# Rev3b_Schematic.net
KiCad netlist of a schematic drawn in Altium Designer
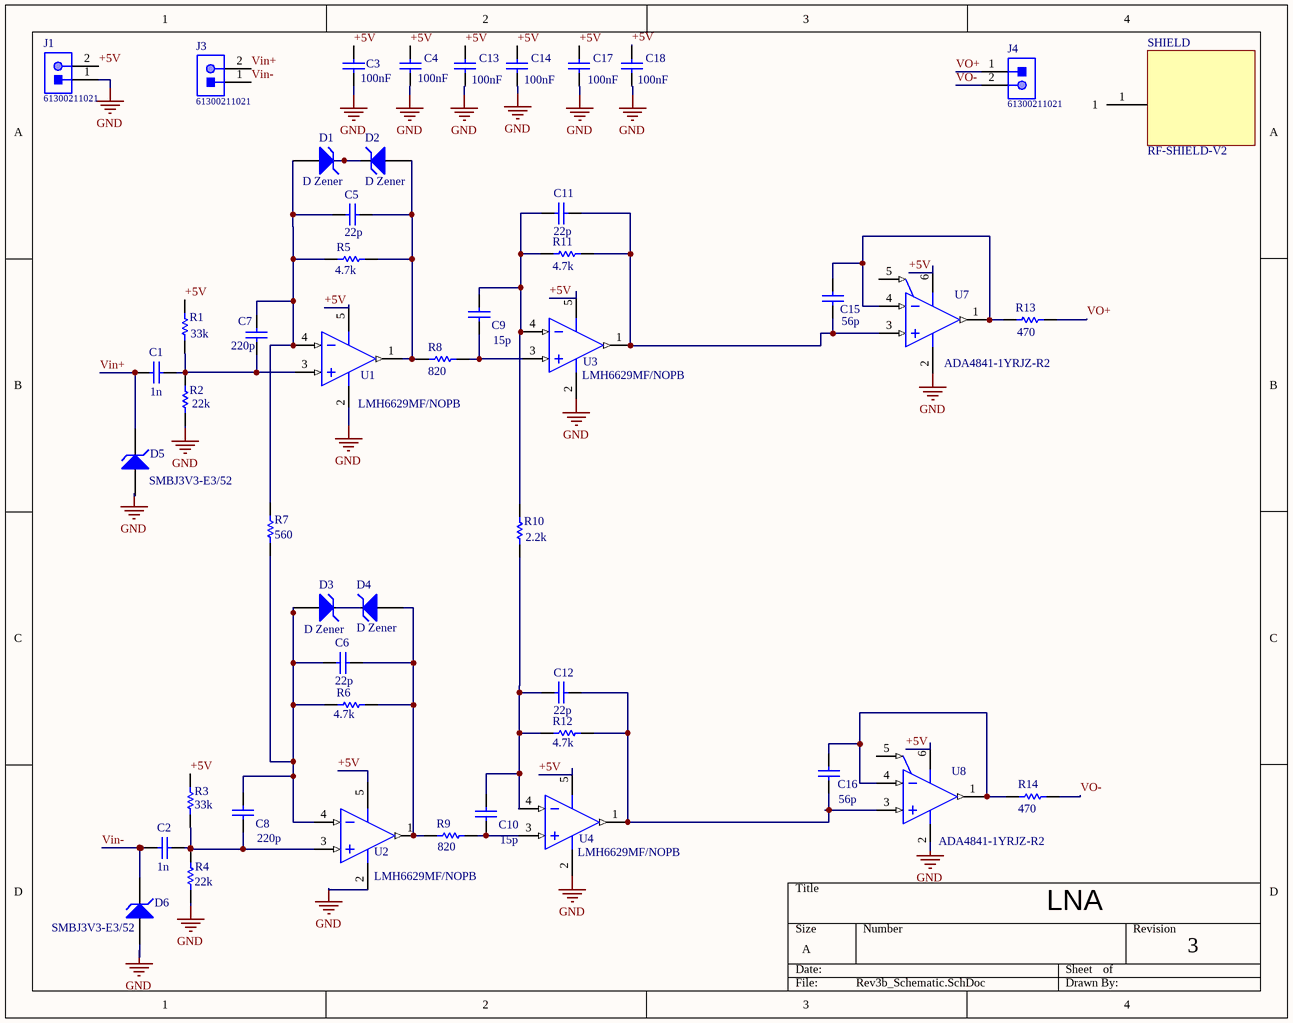
[diagram p0: Rev3b_Schematic.SchDoc]

(export (version "E")
  (design (tool "Eeschema 10.0.6"))
  (components
    (comp (ref "C1")
      (value "1n")
      (footprint "*CAPC1608X90")
      (description "Capacitor")
      (fields (field (name "PUBLISHER") "Altium Limited"))
      (libsource (lib "Miscellaneous Devices") (part "Cap"))
    )
    (comp (ref "C2")
      (value "1n")
      (footprint "*CAPC1608X90")
      (description "Capacitor")
      (fields (field (name "PUBLISHER") "Altium Limited"))
      (libsource (lib "Miscellaneous Devices") (part "Cap"))
    )
    (comp (ref "C3")
      (value "100nF")
      (footprint "*CAPC1608X90")
      (description "Capacitor")
      (fields (field (name "PUBLISHER") "Altium Limited"))
      (libsource (lib "Miscellaneous Devices") (part "Cap"))
    )
    (comp (ref "C4")
      (value "100nF")
      (footprint "*CAPC1608X90")
      (description "Capacitor")
      (fields (field (name "PUBLISHER") "Altium Limited"))
      (libsource (lib "Miscellaneous Devices") (part "Cap"))
    )
    (comp (ref "C5")
      (value "22p")
      (footprint "CAPC1608X90X35LL10T15")
      (fields (field (name "PART NUMBER") "GRM1885C1H100JA01D") (field (name "MANUFACTURER") "Murata"))
      (libsource (lib "Altium Content Vault") (part "CAP"))
    )
    (comp (ref "C6")
      (value "22p")
      (footprint "CAPC1608X90X35LL10T15")
      (fields (field (name "PART NUMBER") "GRM1885C1H100JA01D") (field (name "MANUFACTURER") "Murata"))
      (libsource (lib "Altium Content Vault") (part "CAP"))
    )
    (comp (ref "C7")
      (value "220p")
      (footprint "CAPC1608X87X35NL15T15")
      (fields (field (name "PART NUMBER") "C0603C331J5GACTU") (field (name "MANUFACTURER") "Kemet"))
      (libsource (lib "Altium Content Vault") (part "CAP"))
    )
    (comp (ref "C8")
      (value "220p")
      (footprint "CAPC1608X87X35NL15T15")
      (fields (field (name "PART NUMBER") "C0603C331J5GACTU") (field (name "MANUFACTURER") "Kemet"))
      (libsource (lib "Altium Content Vault") (part "CAP"))
    )
    (comp (ref "C9")
      (value "15p")
      (footprint "CAPC1608X87X35NL15T15")
      (fields (field (name "PART NUMBER") "C0603C331J5GACTU") (field (name "MANUFACTURER") "Kemet"))
      (libsource (lib "Altium Content Vault") (part "CAP"))
    )
    (comp (ref "C10")
      (value "15p")
      (footprint "CAPC1608X87X35NL15T15")
      (fields (field (name "PART NUMBER") "C0603C331J5GACTU") (field (name "MANUFACTURER") "Kemet"))
      (libsource (lib "Altium Content Vault") (part "CAP"))
    )
    (comp (ref "C11")
      (value "22p")
      (footprint "CAPC1608X90X35LL10T15")
      (fields (field (name "PART NUMBER") "GRM1885C1H100JA01D") (field (name "MANUFACTURER") "Murata"))
      (libsource (lib "Altium Content Vault") (part "CAP"))
    )
    (comp (ref "C12")
      (value "22p")
      (footprint "CAPC1608X90X35LL10T15")
      (fields (field (name "PART NUMBER") "GRM1885C1H100JA01D") (field (name "MANUFACTURER") "Murata"))
      (libsource (lib "Altium Content Vault") (part "CAP"))
    )
    (comp (ref "C13")
      (value "100nF")
      (footprint "*CAPC1608X90")
      (description "Capacitor")
      (fields (field (name "PUBLISHER") "Altium Limited"))
      (libsource (lib "Miscellaneous Devices") (part "Cap"))
    )
    (comp (ref "C14")
      (value "100nF")
      (footprint "*CAPC1608X90")
      (description "Capacitor")
      (fields (field (name "PUBLISHER") "Altium Limited"))
      (libsource (lib "Miscellaneous Devices") (part "Cap"))
    )
    (comp (ref "C15")
      (value "56p")
      (footprint "CAPC1608X87X35NL15T15")
      (fields (field (name "PART NUMBER") "C0603C331J5GACTU") (field (name "MANUFACTURER") "Kemet"))
      (libsource (lib "Altium Content Vault") (part "CAP"))
    )
    (comp (ref "C16")
      (value "56p")
      (footprint "CAPC1608X87X35NL15T15")
      (fields (field (name "PART NUMBER") "C0603C331J5GACTU") (field (name "MANUFACTURER") "Kemet"))
      (libsource (lib "Altium Content Vault") (part "CAP"))
    )
    (comp (ref "C17")
      (value "100nF")
      (footprint "*CAPC1608X90")
      (description "Capacitor")
      (fields (field (name "PUBLISHER") "Altium Limited"))
      (libsource (lib "Miscellaneous Devices") (part "Cap"))
    )
    (comp (ref "C18")
      (value "100nF")
      (footprint "*CAPC1608X90")
      (description "Capacitor")
      (fields (field (name "PUBLISHER") "Altium Limited"))
      (libsource (lib "Miscellaneous Devices") (part "Cap"))
    )
    (comp (ref "D1")
      (value "D Zener")
      (footprint "J1-0603")
      (description "Zener Diode")
      (fields (field (name "PUBLISHER") "Altium Limited"))
      (libsource (lib "Miscellaneous Devices") (part "D Zener"))
    )
    (comp (ref "D2")
      (value "D Zener")
      (footprint "J1-0603")
      (description "Zener Diode")
      (fields (field (name "PUBLISHER") "Altium Limited"))
      (libsource (lib "Miscellaneous Devices") (part "D Zener"))
    )
    (comp (ref "D3")
      (value "D Zener")
      (footprint "J1-0603")
      (description "Zener Diode")
      (fields (field (name "PUBLISHER") "Altium Limited"))
      (libsource (lib "Miscellaneous Devices") (part "D Zener"))
    )
    (comp (ref "D4")
      (value "D Zener")
      (footprint "J1-0603")
      (description "Zener Diode")
      (fields (field (name "PUBLISHER") "Altium Limited"))
      (libsource (lib "Miscellaneous Devices") (part "D Zener"))
    )
    (comp (ref "D5")
      (value "SMBJ3V3-E3/52")
      (footprint "VISH-DO-214AA-2_V")
      (fields (field (name "MANUFACTURER") "Vishay"))
      (libsource (lib "Altium Content Vault") (part "DZEN-AK-2"))
    )
    (comp (ref "D6")
      (value "SMBJ3V3-E3/52")
      (footprint "VISH-DO-214AA-2_V")
      (fields (field (name "MANUFACTURER") "Vishay"))
      (libsource (lib "Altium Content Vault") (part "DZEN-AK-2"))
    )
    (comp (ref "J1")
      (value "61300211021")
      (footprint "61300211021")
      (description "THT Angled Pin Header WR-PHD, Pitch 2.54 mm, Single Row, 2 pins")
      (fields (field (name "MANUFACTURER") "Wurth Elektronik") (field (name "PUBLISHER") "WurthElektronik"))
      (libsource (lib "") (part "WE-CN-1P-M-R2_1"))
    )
    (comp (ref "J3")
      (value "61300211021")
      (footprint "61300211021")
      (description "THT Angled Pin Header WR-PHD, Pitch 2.54 mm, Single Row, 2 pins")
      (fields (field (name "MANUFACTURER") "Wurth Elektronik") (field (name "PUBLISHER") "WurthElektronik"))
      (libsource (lib "") (part "WE-CN-1P-M-R2_1"))
    )
    (comp (ref "J4")
      (value "61300211021")
      (footprint "61300211021")
      (description "THT Angled Pin Header WR-PHD, Pitch 2.54 mm, Single Row, 2 pins")
      (fields (field (name "MANUFACTURER") "Wurth Elektronik") (field (name "PUBLISHER") "WurthElektronik"))
      (libsource (lib "Altium Content Vault") (part "WE-CN-1P-M-R2"))
    )
    (comp (ref "R1")
      (value "33k")
      (footprint "J1-0603")
      (description "Resistor")
      (fields (field (name "PUBLISHER") "Altium Limited"))
      (libsource (lib "Miscellaneous Devices") (part "Res1"))
    )
    (comp (ref "R2")
      (value "22k")
      (footprint "J1-0603")
      (description "Resistor")
      (fields (field (name "PUBLISHER") "Altium Limited"))
      (libsource (lib "Miscellaneous Devices") (part "Res1"))
    )
    (comp (ref "R3")
      (value "33k")
      (footprint "J1-0603")
      (description "Resistor")
      (fields (field (name "PUBLISHER") "Altium Limited"))
      (libsource (lib "Miscellaneous Devices") (part "Res1"))
    )
    (comp (ref "R4")
      (value "22k")
      (footprint "J1-0603")
      (description "Resistor")
      (fields (field (name "PUBLISHER") "Altium Limited"))
      (libsource (lib "Miscellaneous Devices") (part "Res1"))
    )
    (comp (ref "R5")
      (value "4.7k")
      (footprint "J1-0603")
      (description "Resistor")
      (fields (field (name "PUBLISHER") "Altium Limited"))
      (libsource (lib "Miscellaneous Devices") (part "Res1"))
    )
    (comp (ref "R6")
      (value "4.7k")
      (footprint "J1-0603")
      (description "Resistor")
      (fields (field (name "PUBLISHER") "Altium Limited"))
      (libsource (lib "Miscellaneous Devices") (part "Res1"))
    )
    (comp (ref "R7")
      (value "560")
      (footprint "J1-0603")
      (description "Resistor")
      (fields (field (name "PUBLISHER") "Altium Limited"))
      (libsource (lib "Miscellaneous Devices") (part "Res1"))
    )
    (comp (ref "R8")
      (value "820")
      (footprint "J1-0603")
      (description "Resistor")
      (fields (field (name "PUBLISHER") "Altium Limited"))
      (libsource (lib "Miscellaneous Devices") (part "Res1"))
    )
    (comp (ref "R9")
      (value "820")
      (footprint "J1-0603")
      (description "Resistor")
      (fields (field (name "PUBLISHER") "Altium Limited"))
      (libsource (lib "Miscellaneous Devices") (part "Res1"))
    )
    (comp (ref "R10")
      (value "2.2k")
      (footprint "J1-0603")
      (description "Resistor")
      (fields (field (name "PUBLISHER") "Altium Limited"))
      (libsource (lib "Miscellaneous Devices") (part "Res1"))
    )
    (comp (ref "R11")
      (value "4.7k")
      (footprint "J1-0603")
      (description "Resistor")
      (fields (field (name "PUBLISHER") "Altium Limited"))
      (libsource (lib "Miscellaneous Devices") (part "Res1"))
    )
    (comp (ref "R12")
      (value "4.7k")
      (footprint "J1-0603")
      (description "Resistor")
      (fields (field (name "PUBLISHER") "Altium Limited"))
      (libsource (lib "Miscellaneous Devices") (part "Res1"))
    )
    (comp (ref "R13")
      (value "470")
      (footprint "J1-0603")
      (description "Resistor")
      (fields (field (name "PUBLISHER") "Altium Limited"))
      (libsource (lib "Miscellaneous Devices") (part "Res1"))
    )
    (comp (ref "R14")
      (value "470")
      (footprint "J1-0603")
      (description "Resistor")
      (fields (field (name "PUBLISHER") "Altium Limited"))
      (libsource (lib "Miscellaneous Devices") (part "Res1"))
    )
    (comp (ref "SHIELD")
      (value "RF-SHIELD-V2")
      (footprint "RF-SHIELD-V2")
      (libsource (lib "RF-SHIELD-V2") (part "RF-SHIELD-V2"))
    )
    (comp (ref "U1")
      (value "LMH6629MF/NOPB")
      (footprint "DBV0005A_M")
      (description "Ultra-Low Noise, High-Speed Operational Amplifier with Shutdown, 5-pin SOT-23, 1000 Reel")
      (fields (field (name "MANUFACTURER") "Texas Instruments"))
      (libsource (lib "Altium Content Vault") (part "AMP-OPA-LMH6629-5"))
    )
    (comp (ref "U2")
      (value "LMH6629MF/NOPB")
      (footprint "DBV0005A_M")
      (description "Ultra-Low Noise, High-Speed Operational Amplifier with Shutdown, 5-pin SOT-23, 1000 Reel")
      (fields (field (name "MANUFACTURER") "Texas Instruments"))
      (libsource (lib "Altium Content Vault") (part "AMP-OPA-LMH6629-5"))
    )
    (comp (ref "U3")
      (value "LMH6629MF/NOPB")
      (footprint "DBV0005A_M")
      (description "Ultra-Low Noise, High-Speed Operational Amplifier with Shutdown, 5-pin SOT-23, 1000 Reel")
      (fields (field (name "MANUFACTURER") "Texas Instruments"))
      (libsource (lib "Altium Content Vault") (part "AMP-OPA-LMH6629-5"))
    )
    (comp (ref "U4")
      (value "LMH6629MF/NOPB")
      (footprint "DBV0005A_M")
      (description "Ultra-Low Noise, High-Speed Operational Amplifier with Shutdown, 5-pin SOT-23, 1000 Reel")
      (fields (field (name "MANUFACTURER") "Texas Instruments"))
      (libsource (lib "Altium Content Vault") (part "AMP-OPA-LMH6629-5"))
    )
    (comp (ref "U7")
      (value "ADA4841-1YRJZ-R2")
      (footprint "ADI-RJ-6_M")
      (fields (field (name "MANUFACTURER") "Analog Devices") (field (name "GENERIC PART NUMBER") "ADA4841-1"))
      (libsource (lib "Altium Content Vault") (part "ADI-ADA48X1-1-RJ-6"))
    )
    (comp (ref "U8")
      (value "ADA4841-1YRJZ-R2")
      (footprint "ADI-RJ-6_M")
      (fields (field (name "MANUFACTURER") "Analog Devices") (field (name "GENERIC PART NUMBER") "ADA4841-1"))
      (libsource (lib "Altium Content Vault") (part "ADI-ADA48X1-1-RJ-6"))
    )
  )
  (nets
    (net (code "1") (name "/+5V") (class "Default")
      (node (ref "C13") (pin "2") (pinfunction "2_2") (pintype "passive"))
      (node (ref "C14") (pin "2") (pinfunction "2_2") (pintype "passive"))
      (node (ref "C17") (pin "2") (pinfunction "2_2") (pintype "passive"))
      (node (ref "C18") (pin "2") (pinfunction "2_2") (pintype "passive"))
      (node (ref "C3") (pin "2") (pinfunction "2_2") (pintype "passive"))
      (node (ref "C4") (pin "2") (pinfunction "2_2") (pintype "passive"))
      (node (ref "J1") (pin "2") (pinfunction "2_2") (pintype "passive"))
      (node (ref "R1") (pin "2") (pinfunction "2_2") (pintype "passive"))
      (node (ref "R3") (pin "2") (pinfunction "2_2") (pintype "passive"))
      (node (ref "U1") (pin "5") (pinfunction "V+_5") (pintype "power_in"))
      (node (ref "U2") (pin "5") (pinfunction "V+_5") (pintype "power_in"))
      (node (ref "U3") (pin "5") (pinfunction "V+_5") (pintype "power_in"))
      (node (ref "U4") (pin "5") (pinfunction "V+_5") (pintype "power_in"))
      (node (ref "U7") (pin "6") (pinfunction "+VS_6") (pintype "power_in"))
      (node (ref "U8") (pin "6") (pinfunction "+VS_6") (pintype "power_in"))
    )
    (net (code "2") (name "/VO+") (class "Default")
      (node (ref "J4") (pin "1") (pinfunction "1_1") (pintype "passive"))
      (node (ref "R13") (pin "1") (pinfunction "1_1") (pintype "passive"))
    )
    (net (code "3") (name "/VO-") (class "Default")
      (node (ref "J4") (pin "2") (pinfunction "2_2") (pintype "passive"))
      (node (ref "R14") (pin "1") (pinfunction "1_1") (pintype "passive"))
    )
    (net (code "4") (name "/Vin+") (class "Default")
      (node (ref "C1") (pin "2") (pinfunction "2_2") (pintype "passive"))
      (node (ref "D5") (pin "2") (pinfunction "K_2") (pintype "passive"))
      (node (ref "J3") (pin "2") (pinfunction "2_2") (pintype "passive"))
    )
    (net (code "5") (name "/Vin-") (class "Default")
      (node (ref "C2") (pin "2") (pinfunction "2_2") (pintype "passive"))
      (node (ref "D6") (pin "2") (pinfunction "K_2") (pintype "passive"))
      (node (ref "J3") (pin "1") (pinfunction "1_1") (pintype "passive"))
    )
    (net (code "6") (name "GND") (class "Default")
      (node (ref "C13") (pin "1") (pinfunction "1_1") (pintype "passive"))
      (node (ref "C14") (pin "1") (pinfunction "1_1") (pintype "passive"))
      (node (ref "C17") (pin "1") (pinfunction "1_1") (pintype "passive"))
      (node (ref "C18") (pin "1") (pinfunction "1_1") (pintype "passive"))
      (node (ref "C3") (pin "1") (pinfunction "1_1") (pintype "passive"))
      (node (ref "C4") (pin "1") (pinfunction "1_1") (pintype "passive"))
      (node (ref "D5") (pin "1") (pinfunction "A_1") (pintype "passive"))
      (node (ref "D6") (pin "1") (pinfunction "A_1") (pintype "passive"))
      (node (ref "J1") (pin "1") (pinfunction "1_1") (pintype "passive"))
      (node (ref "R2") (pin "1") (pinfunction "1_1") (pintype "passive"))
      (node (ref "R4") (pin "1") (pinfunction "1_1") (pintype "passive"))
      (node (ref "U1") (pin "2") (pinfunction "V-_2") (pintype "power_in"))
      (node (ref "U2") (pin "2") (pinfunction "V-_2") (pintype "power_in"))
      (node (ref "U3") (pin "2") (pinfunction "V-_2") (pintype "power_in"))
      (node (ref "U4") (pin "2") (pinfunction "V-_2") (pintype "power_in"))
      (node (ref "U7") (pin "2") (pinfunction "-VS_2") (pintype "power_in"))
      (node (ref "U8") (pin "2") (pinfunction "-VS_2") (pintype "power_in"))
    )
    (net (code "7") (name "Net-(D1-A)") (class "Default")
      (node (ref "C5") (pin "1") (pinfunction "1_1") (pintype "passive"))
      (node (ref "C7") (pin "2") (pinfunction "2_2") (pintype "passive"))
      (node (ref "D1") (pin "1") (pinfunction "A_1") (pintype "passive"))
      (node (ref "R5") (pin "1") (pinfunction "1_1") (pintype "passive"))
      (node (ref "R7") (pin "2") (pinfunction "2_2") (pintype "passive"))
      (node (ref "U1") (pin "4") (pinfunction "IN-_4") (pintype "input"))
    )
    (net (code "8") (name "Net-(D1-K)") (class "Default")
      (node (ref "D1") (pin "2") (pinfunction "K_2") (pintype "passive"))
      (node (ref "D2") (pin "2") (pinfunction "K_2") (pintype "passive"))
    )
    (net (code "9") (name "Net-(D2-A)") (class "Default")
      (node (ref "C5") (pin "2") (pinfunction "2_2") (pintype "passive"))
      (node (ref "D2") (pin "1") (pinfunction "A_1") (pintype "passive"))
      (node (ref "R5") (pin "2") (pinfunction "2_2") (pintype "passive"))
      (node (ref "R8") (pin "1") (pinfunction "1_1") (pintype "passive"))
      (node (ref "U1") (pin "1") (pinfunction "OUT_1") (pintype "output"))
    )
    (net (code "10") (name "Net-(D3-A)") (class "Default")
      (node (ref "C6") (pin "1") (pinfunction "1_1") (pintype "passive"))
      (node (ref "C8") (pin "2") (pinfunction "2_2") (pintype "passive"))
      (node (ref "D3") (pin "1") (pinfunction "A_1") (pintype "passive"))
      (node (ref "R6") (pin "1") (pinfunction "1_1") (pintype "passive"))
      (node (ref "R7") (pin "1") (pinfunction "1_1") (pintype "passive"))
      (node (ref "U2") (pin "4") (pinfunction "IN-_4") (pintype "input"))
    )
    (net (code "11") (name "Net-(D3-K)") (class "Default")
      (node (ref "D3") (pin "2") (pinfunction "K_2") (pintype "passive"))
      (node (ref "D4") (pin "2") (pinfunction "K_2") (pintype "passive"))
    )
    (net (code "12") (name "Net-(D4-A)") (class "Default")
      (node (ref "C6") (pin "2") (pinfunction "2_2") (pintype "passive"))
      (node (ref "D4") (pin "1") (pinfunction "A_1") (pintype "passive"))
      (node (ref "R6") (pin "2") (pinfunction "2_2") (pintype "passive"))
      (node (ref "R9") (pin "1") (pinfunction "1_1") (pintype "passive"))
      (node (ref "U2") (pin "1") (pinfunction "OUT_1") (pintype "output"))
    )
    (net (code "13") (name "Net-(U1-IN+)") (class "Default")
      (node (ref "C1") (pin "1") (pinfunction "1_1") (pintype "passive"))
      (node (ref "C7") (pin "1") (pinfunction "1_1") (pintype "passive"))
      (node (ref "R1") (pin "1") (pinfunction "1_1") (pintype "passive"))
      (node (ref "R2") (pin "2") (pinfunction "2_2") (pintype "passive"))
      (node (ref "U1") (pin "3") (pinfunction "IN+_3") (pintype "input"))
    )
    (net (code "14") (name "Net-(U2-IN+)") (class "Default")
      (node (ref "C2") (pin "1") (pinfunction "1_1") (pintype "passive"))
      (node (ref "C8") (pin "1") (pinfunction "1_1") (pintype "passive"))
      (node (ref "R3") (pin "1") (pinfunction "1_1") (pintype "passive"))
      (node (ref "R4") (pin "2") (pinfunction "2_2") (pintype "passive"))
      (node (ref "U2") (pin "3") (pinfunction "IN+_3") (pintype "input"))
    )
    (net (code "15") (name "Net-(U3-IN+)") (class "Default")
      (node (ref "C9") (pin "1") (pinfunction "1_1") (pintype "passive"))
      (node (ref "R8") (pin "2") (pinfunction "2_2") (pintype "passive"))
      (node (ref "U3") (pin "3") (pinfunction "IN+_3") (pintype "input"))
    )
    (net (code "16") (name "Net-(U3-IN-)") (class "Default")
      (node (ref "C11") (pin "1") (pinfunction "1_1") (pintype "passive"))
      (node (ref "C9") (pin "2") (pinfunction "2_2") (pintype "passive"))
      (node (ref "R10") (pin "2") (pinfunction "2_2") (pintype "passive"))
      (node (ref "R11") (pin "1") (pinfunction "1_1") (pintype "passive"))
      (node (ref "U3") (pin "4") (pinfunction "IN-_4") (pintype "input"))
    )
    (net (code "17") (name "Net-(U3-OUT)") (class "Default")
      (node (ref "C11") (pin "2") (pinfunction "2_2") (pintype "passive"))
      (node (ref "C15") (pin "1") (pinfunction "1_1") (pintype "passive"))
      (node (ref "R11") (pin "2") (pinfunction "2_2") (pintype "passive"))
      (node (ref "U3") (pin "1") (pinfunction "OUT_1") (pintype "output"))
      (node (ref "U7") (pin "3") (pinfunction "+IN_3") (pintype "input"))
    )
    (net (code "18") (name "Net-(U4-IN+)") (class "Default")
      (node (ref "C10") (pin "1") (pinfunction "1_1") (pintype "passive"))
      (node (ref "R9") (pin "2") (pinfunction "2_2") (pintype "passive"))
      (node (ref "U4") (pin "3") (pinfunction "IN+_3") (pintype "input"))
    )
    (net (code "19") (name "Net-(U4-IN-)") (class "Default")
      (node (ref "C10") (pin "2") (pinfunction "2_2") (pintype "passive"))
      (node (ref "C12") (pin "1") (pinfunction "1_1") (pintype "passive"))
      (node (ref "R10") (pin "1") (pinfunction "1_1") (pintype "passive"))
      (node (ref "R12") (pin "1") (pinfunction "1_1") (pintype "passive"))
      (node (ref "U4") (pin "4") (pinfunction "IN-_4") (pintype "input"))
    )
    (net (code "20") (name "Net-(U4-OUT)") (class "Default")
      (node (ref "C12") (pin "2") (pinfunction "2_2") (pintype "passive"))
      (node (ref "C16") (pin "1") (pinfunction "1_1") (pintype "passive"))
      (node (ref "R12") (pin "2") (pinfunction "2_2") (pintype "passive"))
      (node (ref "U4") (pin "1") (pinfunction "OUT_1") (pintype "output"))
      (node (ref "U8") (pin "3") (pinfunction "+IN_3") (pintype "input"))
    )
    (net (code "21") (name "Net-(U7--IN)") (class "Default")
      (node (ref "C15") (pin "2") (pinfunction "2_2") (pintype "passive"))
      (node (ref "R13") (pin "2") (pinfunction "2_2") (pintype "passive"))
      (node (ref "U7") (pin "1") (pinfunction "VOUT_1") (pintype "output"))
      (node (ref "U7") (pin "4") (pinfunction "-IN_4") (pintype "input"))
    )
    (net (code "22") (name "Net-(U8--IN)") (class "Default")
      (node (ref "C16") (pin "2") (pinfunction "2_2") (pintype "passive"))
      (node (ref "R14") (pin "2") (pinfunction "2_2") (pintype "passive"))
      (node (ref "U8") (pin "1") (pinfunction "VOUT_1") (pintype "output"))
      (node (ref "U8") (pin "4") (pinfunction "-IN_4") (pintype "input"))
    )
    (net (code "23") (name "unconnected-(SHIELD-Pad1)") (class "Default")
      (node (ref "SHIELD") (pin "1") (pinfunction "1_1") (pintype "passive"))
    )
    (net (code "24") (name "unconnected-(U7-~{POWER_DOWN}-Pad5)") (class "Default")
      (node (ref "U7") (pin "5") (pinfunction "~{POWER_DOWN}_5") (pintype "input"))
    )
    (net (code "25") (name "unconnected-(U8-~{POWER_DOWN}-Pad5)") (class "Default")
      (node (ref "U8") (pin "5") (pinfunction "~{POWER_DOWN}_5") (pintype "input"))
    )
  )
)
